# mcu_brd3.net
KiCad netlist of a schematic drawn in EAGLE
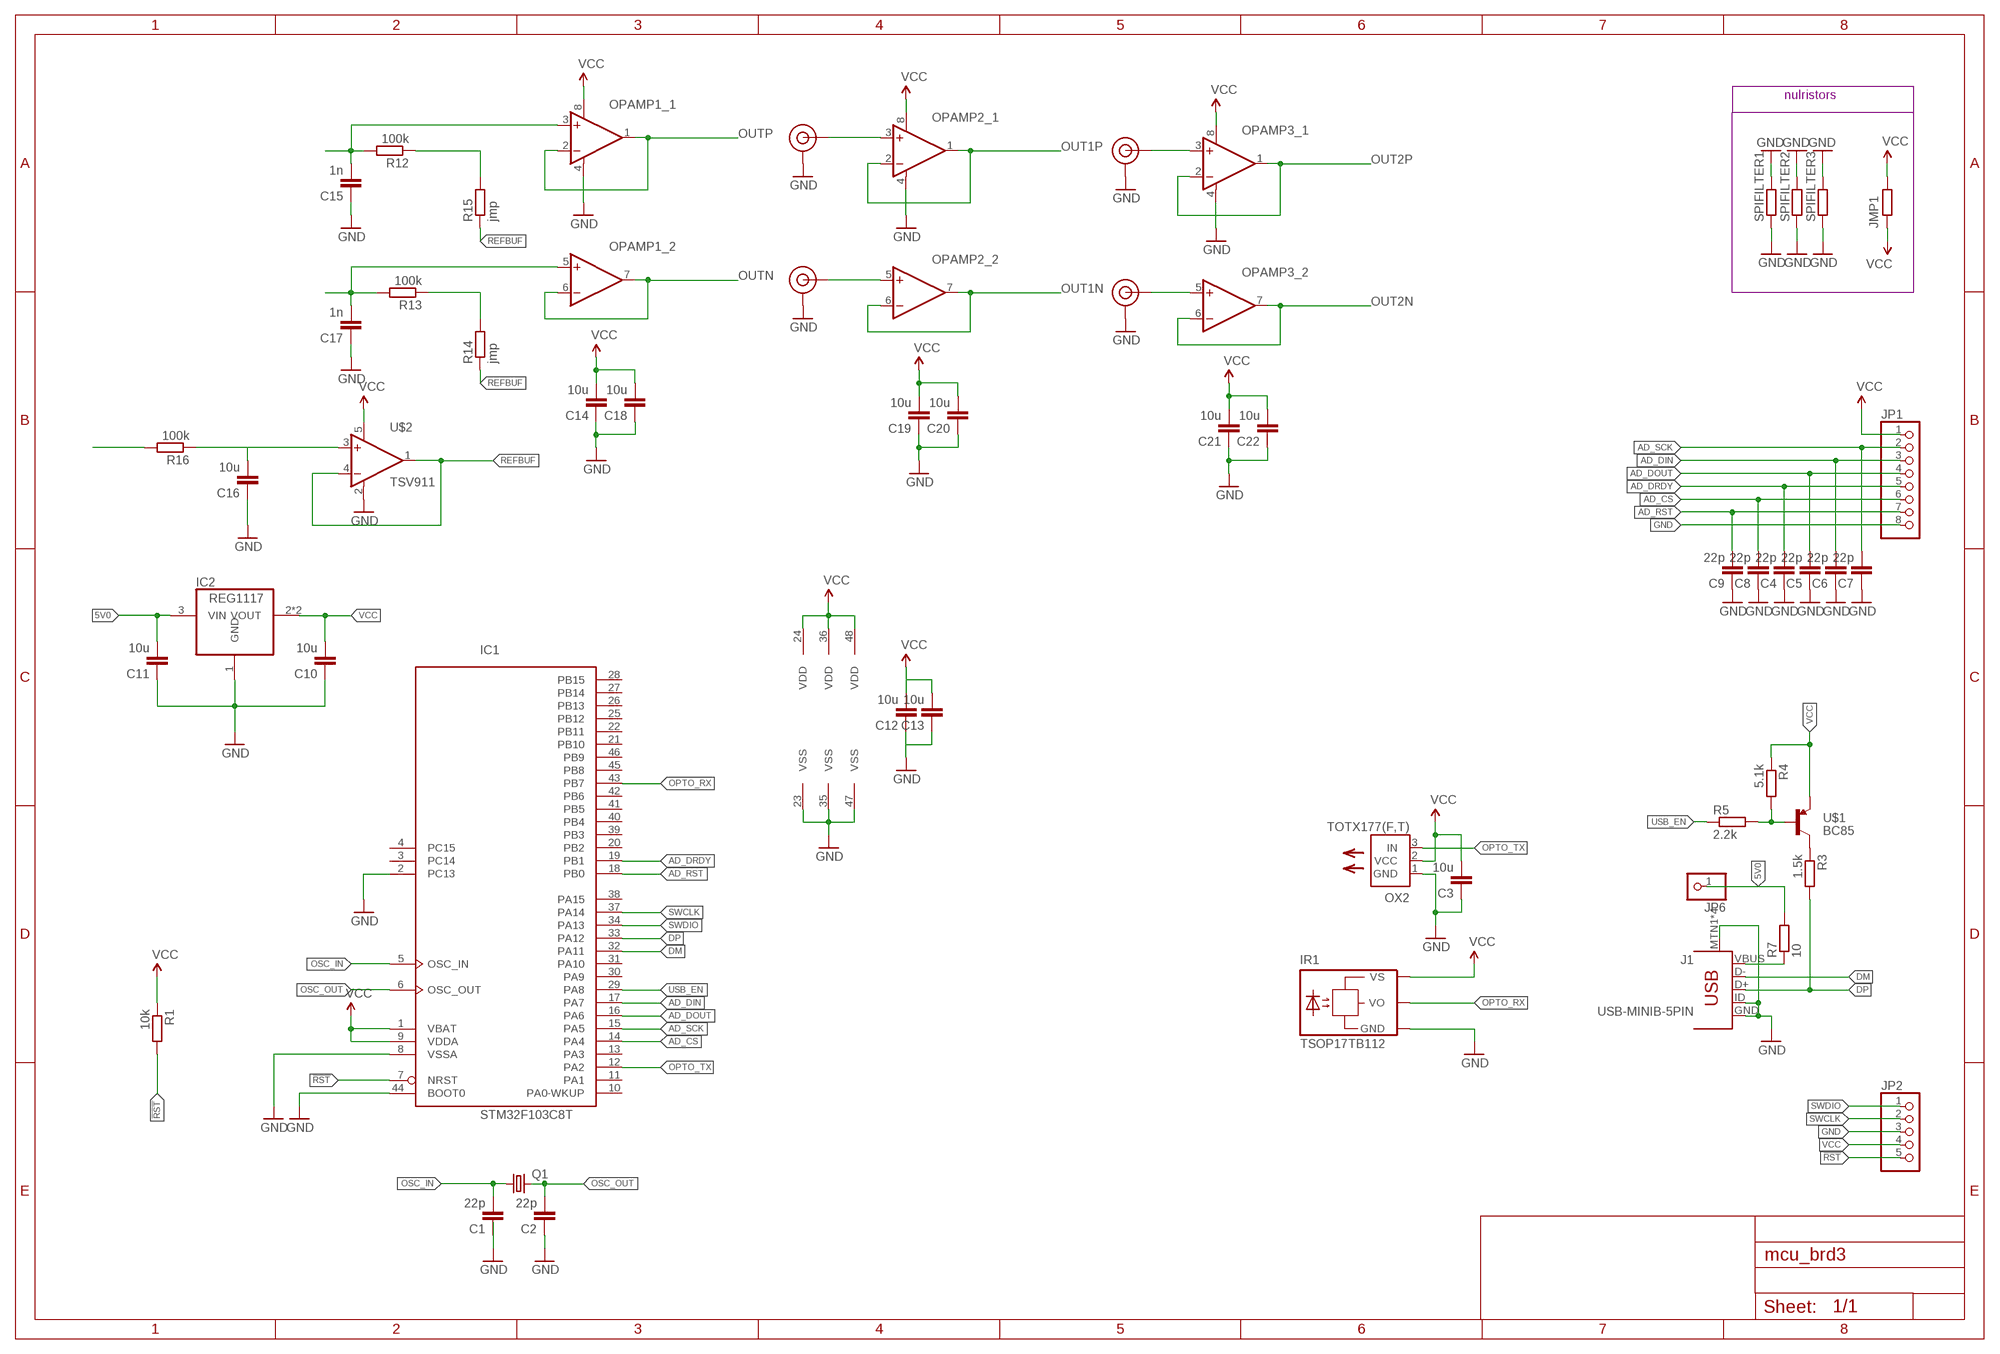
[diagram p0: schematic, sheet 1]

(export (version "E")
  (design (tool "Eeschema 10.0.6"))
  (components
    (comp (ref "C1")
      (value "22p")
      (footprint "eagle-import:C0603")
      (libsource (lib "eagle-import") (part "CC0603"))
    )
    (comp (ref "C2")
      (value "22p")
      (footprint "eagle-import:C0603")
      (libsource (lib "eagle-import") (part "CC0603"))
    )
    (comp (ref "C3")
      (value "10u")
      (footprint "eagle-import:C0603")
      (libsource (lib "eagle-import") (part "CC0603"))
    )
    (comp (ref "C4")
      (value "22p")
      (footprint "eagle-import:C0603")
      (libsource (lib "eagle-import") (part "CC0603"))
    )
    (comp (ref "C5")
      (value "22p")
      (footprint "eagle-import:C0603")
      (libsource (lib "eagle-import") (part "CC0603"))
    )
    (comp (ref "C6")
      (value "22p")
      (footprint "eagle-import:C0603")
      (libsource (lib "eagle-import") (part "CC0603"))
    )
    (comp (ref "C7")
      (value "22p")
      (footprint "eagle-import:C0603")
      (libsource (lib "eagle-import") (part "CC0603"))
    )
    (comp (ref "C8")
      (value "22p")
      (footprint "eagle-import:C0603")
      (libsource (lib "eagle-import") (part "CC0603"))
    )
    (comp (ref "C9")
      (value "22p")
      (footprint "eagle-import:C0603")
      (libsource (lib "eagle-import") (part "CC0603"))
    )
    (comp (ref "C10")
      (value "10u")
      (footprint "eagle-import:C0805")
      (libsource (lib "eagle-import") (part "CC0805"))
    )
    (comp (ref "C11")
      (value "10u")
      (footprint "eagle-import:C0805")
      (libsource (lib "eagle-import") (part "CC0805"))
    )
    (comp (ref "C12")
      (value "10u")
      (footprint "eagle-import:C0805")
      (libsource (lib "eagle-import") (part "CC0805"))
    )
    (comp (ref "C13")
      (value "10u")
      (footprint "eagle-import:C0805")
      (libsource (lib "eagle-import") (part "CC0805"))
    )
    (comp (ref "C14")
      (value "10u")
      (footprint "eagle-import:C0805")
      (libsource (lib "eagle-import") (part "CC0805"))
    )
    (comp (ref "C15")
      (value "1n")
      (footprint "eagle-import:C0603")
      (libsource (lib "eagle-import") (part "CC0603"))
    )
    (comp (ref "C16")
      (value "10u")
      (footprint "eagle-import:C0805")
      (libsource (lib "eagle-import") (part "CC0805"))
    )
    (comp (ref "C17")
      (value "1n")
      (footprint "eagle-import:C0603")
      (libsource (lib "eagle-import") (part "CC0603"))
    )
    (comp (ref "C18")
      (value "10u")
      (footprint "eagle-import:C0805")
      (libsource (lib "eagle-import") (part "CC0805"))
    )
    (comp (ref "C19")
      (value "10u")
      (footprint "eagle-import:C0805")
      (libsource (lib "eagle-import") (part "CC0805"))
    )
    (comp (ref "C20")
      (value "10u")
      (footprint "eagle-import:C0805")
      (libsource (lib "eagle-import") (part "CC0805"))
    )
    (comp (ref "C21")
      (value "10u")
      (footprint "eagle-import:C0805")
      (libsource (lib "eagle-import") (part "CC0805"))
    )
    (comp (ref "C22")
      (value "10u")
      (footprint "eagle-import:C0805")
      (libsource (lib "eagle-import") (part "CC0805"))
    )
    (comp (ref "IC1")
      (value "STM32F103C8T")
      (footprint "eagle-import:LQFP48")
      (libsource (lib "eagle-import") (part "STM32F103CT8"))
    )
    (comp (ref "IC2")
      (value "REG1117")
      (footprint "eagle-import:SOT223")
      (libsource (lib "eagle-import") (part "REG1117"))
    )
    (comp (ref "IR1")
      (value "TSOP17TB112")
      (footprint "eagle-import:1X03")
      (libsource (lib "eagle-import") (part "TSOP17TB112"))
    )
    (comp (ref "J$1")
      (value "SMA_EDGE")
      (footprint "eagle-import:SMA-EDGE")
      (libsource (lib "eagle-import") (part "SMA_EDGE"))
    )
    (comp (ref "J$2")
      (value "SMA_EDGE")
      (footprint "eagle-import:SMA-EDGE")
      (libsource (lib "eagle-import") (part "SMA_EDGE"))
    )
    (comp (ref "J$3")
      (value "SMA_EDGE")
      (footprint "eagle-import:SMA-EDGE")
      (libsource (lib "eagle-import") (part "SMA_EDGE"))
    )
    (comp (ref "J$4")
      (value "SMA_EDGE")
      (footprint "eagle-import:SMA-EDGE")
      (libsource (lib "eagle-import") (part "SMA_EDGE"))
    )
    (comp (ref "J1")
      (value "USB-MINIB-5PIN")
      (footprint "eagle-import:USB-MINIB")
      (libsource (lib "eagle-import") (part "USB-MINIB-5PIN"))
    )
    (comp (ref "JMP1")
      (value "R0603")
      (footprint "eagle-import:0603")
      (libsource (lib "eagle-import") (part "R0603"))
    )
    (comp (ref "JP1")
      (value "PINHD-1X8")
      (footprint "eagle-import:1X08")
      (libsource (lib "eagle-import") (part "PINHD-1X8"))
    )
    (comp (ref "JP2")
      (value "PINHD-1X5")
      (footprint "eagle-import:1X05")
      (libsource (lib "eagle-import") (part "PINHD-1X5"))
    )
    (comp (ref "JP6")
      (value "PINHD-1X1")
      (footprint "eagle-import:1X01")
      (libsource (lib "eagle-import") (part "PINHD-1X1"))
    )
    (comp (ref "OPAMP1")
      (value "LMC662")
      (footprint "eagle-import:SO08")
      (libsource (lib "eagle-import") (part "LMC662"))
    )
    (comp (ref "OPAMP2")
      (value "LMC662")
      (footprint "eagle-import:SO08")
      (libsource (lib "eagle-import") (part "LMC662"))
    )
    (comp (ref "OPAMP3")
      (value "LMC662")
      (footprint "eagle-import:SO08")
      (libsource (lib "eagle-import") (part "LMC662"))
    )
    (comp (ref "OX2")
      (value "TOTX177(F,T)")
      (footprint "eagle-import:TOTX")
      (libsource (lib "eagle-import") (part "TOTX177(F,T)"))
    )
    (comp (ref "Q1")
      (value "CRYSTALHC49UP")
      (footprint "eagle-import:HC49UP")
      (libsource (lib "eagle-import") (part "CRYSTALHC49UP"))
    )
    (comp (ref "R1")
      (value "10k")
      (footprint "eagle-import:0603")
      (libsource (lib "eagle-import") (part "R0603"))
    )
    (comp (ref "R3")
      (value "1.5k")
      (footprint "eagle-import:0603")
      (libsource (lib "eagle-import") (part "R0603"))
    )
    (comp (ref "R4")
      (value "5.1k")
      (footprint "eagle-import:0603")
      (libsource (lib "eagle-import") (part "R0603"))
    )
    (comp (ref "R5")
      (value "2.2k")
      (footprint "eagle-import:0603")
      (libsource (lib "eagle-import") (part "R0603"))
    )
    (comp (ref "R7")
      (value "10")
      (footprint "eagle-import:R0805")
      (libsource (lib "eagle-import") (part "R0805"))
    )
    (comp (ref "R12")
      (value "100k")
      (footprint "eagle-import:0603")
      (libsource (lib "eagle-import") (part "R0603"))
    )
    (comp (ref "R13")
      (value "100k")
      (footprint "eagle-import:0603")
      (libsource (lib "eagle-import") (part "R0603"))
    )
    (comp (ref "R14")
      (value "jmp")
      (footprint "eagle-import:0603")
      (libsource (lib "eagle-import") (part "R0603"))
    )
    (comp (ref "R15")
      (value "jmp")
      (footprint "eagle-import:0603")
      (libsource (lib "eagle-import") (part "R0603"))
    )
    (comp (ref "R16")
      (value "100k")
      (footprint "eagle-import:0603")
      (libsource (lib "eagle-import") (part "R0603"))
    )
    (comp (ref "SPIFILTER1")
      (value "R0603")
      (footprint "eagle-import:0603")
      (libsource (lib "eagle-import") (part "R0603"))
    )
    (comp (ref "SPIFILTER2")
      (value "R0603")
      (footprint "eagle-import:0603")
      (libsource (lib "eagle-import") (part "R0603"))
    )
    (comp (ref "SPIFILTER3")
      (value "R0603")
      (footprint "eagle-import:0603")
      (libsource (lib "eagle-import") (part "R0603"))
    )
    (comp (ref "U$1")
      (value "BC85")
      (footprint "eagle-import:SOT23")
      (libsource (lib "eagle-import") (part "BC85"))
    )
    (comp (ref "U$2")
      (value "TSV911")
      (footprint "eagle-import:SOT23-5L")
      (libsource (lib "eagle-import") (part "TSV911"))
    )
  )
  (nets
    (net (code "1") (name "/OUT1N") (class "Default")
      (node (ref "OPAMP2") (pin "6") (pinfunction "-IN_6") (pintype "input"))
      (node (ref "OPAMP2") (pin "7") (pinfunction "OUT_7") (pintype "output"))
    )
    (net (code "2") (name "/OUT1P") (class "Default")
      (node (ref "OPAMP2") (pin "1") (pinfunction "OUT_1") (pintype "output"))
      (node (ref "OPAMP2") (pin "2") (pinfunction "-IN_2") (pintype "input"))
    )
    (net (code "3") (name "/OUT2N") (class "Default")
      (node (ref "OPAMP3") (pin "6") (pinfunction "-IN_6") (pintype "input"))
      (node (ref "OPAMP3") (pin "7") (pinfunction "OUT_7") (pintype "output"))
    )
    (net (code "4") (name "/OUT2P") (class "Default")
      (node (ref "OPAMP3") (pin "1") (pinfunction "OUT_1") (pintype "output"))
      (node (ref "OPAMP3") (pin "2") (pinfunction "-IN_2") (pintype "input"))
    )
    (net (code "5") (name "/OUTN") (class "Default")
      (node (ref "OPAMP1") (pin "6") (pinfunction "-IN_6") (pintype "input"))
      (node (ref "OPAMP1") (pin "7") (pinfunction "OUT_7") (pintype "output"))
    )
    (net (code "6") (name "/OUTP") (class "Default")
      (node (ref "OPAMP1") (pin "1") (pinfunction "OUT_1") (pintype "output"))
      (node (ref "OPAMP1") (pin "2") (pinfunction "-IN_2") (pintype "input"))
    )
    (net (code "7") (name "/~{RST}") (class "Default")
      (node (ref "IC1") (pin "7") (pinfunction "NRST_7") (pintype "bidirectional"))
      (node (ref "JP2") (pin "5") (pinfunction "5_5") (pintype "passive"))
      (node (ref "R1") (pin "2") (pinfunction "2_2") (pintype "passive"))
    )
    (net (code "8") (name "5V0") (class "Default")
      (node (ref "C11") (pin "2") (pinfunction "2_2") (pintype "passive"))
      (node (ref "IC2") (pin "3") (pinfunction "VIN_3") (pintype "input"))
      (node (ref "JP6") (pin "1") (pinfunction "1_1") (pintype "passive"))
      (node (ref "R7") (pin "2") (pinfunction "2_2") (pintype "passive"))
    )
    (net (code "9") (name "AD_CS") (class "Default")
      (node (ref "C8") (pin "2") (pinfunction "2_2") (pintype "passive"))
      (node (ref "IC1") (pin "14") (pinfunction "PA4_14") (pintype "bidirectional"))
      (node (ref "JP1") (pin "6") (pinfunction "6_6") (pintype "passive"))
    )
    (net (code "10") (name "AD_DIN") (class "Default")
      (node (ref "C6") (pin "2") (pinfunction "2_2") (pintype "passive"))
      (node (ref "IC1") (pin "17") (pinfunction "PA7_17") (pintype "bidirectional"))
      (node (ref "JP1") (pin "3") (pinfunction "3_3") (pintype "passive"))
    )
    (net (code "11") (name "AD_DOUT") (class "Default")
      (node (ref "C5") (pin "2") (pinfunction "2_2") (pintype "passive"))
      (node (ref "IC1") (pin "16") (pinfunction "PA6_16") (pintype "bidirectional"))
      (node (ref "JP1") (pin "4") (pinfunction "4_4") (pintype "passive"))
    )
    (net (code "12") (name "AD_DRDY") (class "Default")
      (node (ref "C4") (pin "2") (pinfunction "2_2") (pintype "passive"))
      (node (ref "IC1") (pin "19") (pinfunction "PB1_19") (pintype "bidirectional"))
      (node (ref "JP1") (pin "5") (pinfunction "5_5") (pintype "passive"))
    )
    (net (code "13") (name "AD_RST") (class "Default")
      (node (ref "C9") (pin "2") (pinfunction "2_2") (pintype "passive"))
      (node (ref "IC1") (pin "18") (pinfunction "PB0_18") (pintype "bidirectional"))
      (node (ref "JP1") (pin "7") (pinfunction "7_7") (pintype "passive"))
    )
    (net (code "14") (name "AD_SCK") (class "Default")
      (node (ref "C7") (pin "2") (pinfunction "2_2") (pintype "passive"))
      (node (ref "IC1") (pin "15") (pinfunction "PA5_15") (pintype "bidirectional"))
      (node (ref "JP1") (pin "2") (pinfunction "2_2") (pintype "passive"))
    )
    (net (code "15") (name "DM") (class "Default")
      (node (ref "IC1") (pin "32") (pinfunction "PA11_32") (pintype "bidirectional"))
      (node (ref "J1") (pin "D-") (pinfunction "D-_D-") (pintype "bidirectional"))
    )
    (net (code "16") (name "DP") (class "Default")
      (node (ref "IC1") (pin "33") (pinfunction "PA12_33") (pintype "bidirectional"))
      (node (ref "J1") (pin "D+") (pinfunction "D+_D+") (pintype "bidirectional"))
      (node (ref "R3") (pin "2") (pinfunction "2_2") (pintype "passive"))
    )
    (net (code "17") (name "GND") (class "Default")
      (node (ref "C1") (pin "1") (pinfunction "1_1") (pintype "passive"))
      (node (ref "C10") (pin "1") (pinfunction "1_1") (pintype "passive"))
      (node (ref "C11") (pin "1") (pinfunction "1_1") (pintype "passive"))
      (node (ref "C12") (pin "1") (pinfunction "1_1") (pintype "passive"))
      (node (ref "C13") (pin "1") (pinfunction "1_1") (pintype "passive"))
      (node (ref "C14") (pin "1") (pinfunction "1_1") (pintype "passive"))
      (node (ref "C15") (pin "1") (pinfunction "1_1") (pintype "passive"))
      (node (ref "C16") (pin "1") (pinfunction "1_1") (pintype "passive"))
      (node (ref "C17") (pin "1") (pinfunction "1_1") (pintype "passive"))
      (node (ref "C18") (pin "1") (pinfunction "1_1") (pintype "passive"))
      (node (ref "C19") (pin "1") (pinfunction "1_1") (pintype "passive"))
      (node (ref "C2") (pin "1") (pinfunction "1_1") (pintype "passive"))
      (node (ref "C20") (pin "1") (pinfunction "1_1") (pintype "passive"))
      (node (ref "C21") (pin "1") (pinfunction "1_1") (pintype "passive"))
      (node (ref "C22") (pin "1") (pinfunction "1_1") (pintype "passive"))
      (node (ref "C3") (pin "1") (pinfunction "1_1") (pintype "passive"))
      (node (ref "C4") (pin "1") (pinfunction "1_1") (pintype "passive"))
      (node (ref "C5") (pin "1") (pinfunction "1_1") (pintype "passive"))
      (node (ref "C6") (pin "1") (pinfunction "1_1") (pintype "passive"))
      (node (ref "C7") (pin "1") (pinfunction "1_1") (pintype "passive"))
      (node (ref "C8") (pin "1") (pinfunction "1_1") (pintype "passive"))
      (node (ref "C9") (pin "1") (pinfunction "1_1") (pintype "passive"))
      (node (ref "IC1") (pin "2") (pinfunction "PC13_2") (pintype "bidirectional"))
      (node (ref "IC1") (pin "23") (pinfunction "VSS_23") (pintype "power_in"))
      (node (ref "IC1") (pin "35") (pinfunction "VSS_35") (pintype "power_in"))
      (node (ref "IC1") (pin "44") (pinfunction "BOOT0_44") (pintype "input"))
      (node (ref "IC1") (pin "47") (pinfunction "VSS_47") (pintype "power_in"))
      (node (ref "IC1") (pin "8") (pinfunction "VSSA_8") (pintype "power_in"))
      (node (ref "IC2") (pin "1") (pinfunction "GND_1") (pintype "power_in"))
      (node (ref "IR1") (pin "3") (pinfunction "GND_3") (pintype "power_in"))
      (node (ref "J$1") (pin "GND@0") (pinfunction "GND_GND@0") (pintype "bidirectional"))
      (node (ref "J$1") (pin "GND@1") (pinfunction "GND_GND@1") (pintype "bidirectional"))
      (node (ref "J$1") (pin "GND@2") (pinfunction "GND_GND@2") (pintype "bidirectional"))
      (node (ref "J$1") (pin "GND@3") (pinfunction "GND_GND@3") (pintype "bidirectional"))
      (node (ref "J$2") (pin "GND@0") (pinfunction "GND_GND@0") (pintype "bidirectional"))
      (node (ref "J$2") (pin "GND@1") (pinfunction "GND_GND@1") (pintype "bidirectional"))
      (node (ref "J$2") (pin "GND@2") (pinfunction "GND_GND@2") (pintype "bidirectional"))
      (node (ref "J$2") (pin "GND@3") (pinfunction "GND_GND@3") (pintype "bidirectional"))
      (node (ref "J$3") (pin "GND@0") (pinfunction "GND_GND@0") (pintype "bidirectional"))
      (node (ref "J$3") (pin "GND@1") (pinfunction "GND_GND@1") (pintype "bidirectional"))
      (node (ref "J$3") (pin "GND@2") (pinfunction "GND_GND@2") (pintype "bidirectional"))
      (node (ref "J$3") (pin "GND@3") (pinfunction "GND_GND@3") (pintype "bidirectional"))
      (node (ref "J$4") (pin "GND@0") (pinfunction "GND_GND@0") (pintype "bidirectional"))
      (node (ref "J$4") (pin "GND@1") (pinfunction "GND_GND@1") (pintype "bidirectional"))
      (node (ref "J$4") (pin "GND@2") (pinfunction "GND_GND@2") (pintype "bidirectional"))
      (node (ref "J$4") (pin "GND@3") (pinfunction "GND_GND@3") (pintype "bidirectional"))
      (node (ref "J1") (pin "GND") (pinfunction "GND_GND") (pintype "bidirectional"))
      (node (ref "J1") (pin "ID") (pinfunction "ID_ID") (pintype "bidirectional"))
      (node (ref "J1") (pin "MTN1") (pinfunction "MTN1_MTN1") (pintype "bidirectional"))
      (node (ref "J1") (pin "MTN2") (pinfunction "MTN1_MTN2") (pintype "bidirectional"))
      (node (ref "J1") (pin "MTN3") (pinfunction "MTN1_MTN3") (pintype "bidirectional"))
      (node (ref "J1") (pin "MTN4") (pinfunction "MTN1_MTN4") (pintype "bidirectional"))
      (node (ref "JP1") (pin "8") (pinfunction "8_8") (pintype "passive"))
      (node (ref "JP2") (pin "3") (pinfunction "3_3") (pintype "passive"))
      (node (ref "OPAMP1") (pin "4") (pinfunction "V-_4") (pintype "power_in"))
      (node (ref "OPAMP2") (pin "4") (pinfunction "V-_4") (pintype "power_in"))
      (node (ref "OPAMP3") (pin "4") (pinfunction "V-_4") (pintype "power_in"))
      (node (ref "OX2") (pin "1") (pinfunction "GND_1") (pintype "power_in"))
      (node (ref "SPIFILTER1") (pin "1") (pinfunction "1_1") (pintype "passive"))
      (node (ref "SPIFILTER1") (pin "2") (pinfunction "2_2") (pintype "passive"))
      (node (ref "SPIFILTER2") (pin "1") (pinfunction "1_1") (pintype "passive"))
      (node (ref "SPIFILTER2") (pin "2") (pinfunction "2_2") (pintype "passive"))
      (node (ref "SPIFILTER3") (pin "1") (pinfunction "1_1") (pintype "passive"))
      (node (ref "SPIFILTER3") (pin "2") (pinfunction "2_2") (pintype "passive"))
      (node (ref "U$2") (pin "2") (pinfunction "V-_2") (pintype "power_in"))
    )
    (net (code "18") (name "Net-(J$1-SIGNAL)") (class "Default")
      (node (ref "J$1") (pin "SIG") (pinfunction "SIGNAL_SIG") (pintype "bidirectional"))
      (node (ref "OPAMP2") (pin "3") (pinfunction "+IN_3") (pintype "input"))
    )
    (net (code "19") (name "Net-(J$2-SIGNAL)") (class "Default")
      (node (ref "J$2") (pin "SIG") (pinfunction "SIGNAL_SIG") (pintype "bidirectional"))
      (node (ref "OPAMP2") (pin "5") (pinfunction "+IN_5") (pintype "input"))
    )
    (net (code "20") (name "Net-(J$3-SIGNAL)") (class "Default")
      (node (ref "J$3") (pin "SIG") (pinfunction "SIGNAL_SIG") (pintype "bidirectional"))
      (node (ref "OPAMP3") (pin "3") (pinfunction "+IN_3") (pintype "input"))
    )
    (net (code "21") (name "Net-(J$4-SIGNAL)") (class "Default")
      (node (ref "J$4") (pin "SIG") (pinfunction "SIGNAL_SIG") (pintype "bidirectional"))
      (node (ref "OPAMP3") (pin "5") (pinfunction "+IN_5") (pintype "input"))
    )
    (net (code "22") (name "Net-(J1-PadVBUS)") (class "Default")
      (node (ref "J1") (pin "VBUS") (pinfunction "VBUS_VBUS") (pintype "bidirectional"))
      (node (ref "R7") (pin "1") (pinfunction "1_1") (pintype "passive"))
    )
    (net (code "23") (name "Net-(OPAMP1A-+IN)") (class "Default")
      (node (ref "C15") (pin "2") (pinfunction "2_2") (pintype "passive"))
      (node (ref "OPAMP1") (pin "3") (pinfunction "+IN_3") (pintype "input"))
      (node (ref "R12") (pin "2") (pinfunction "2_2") (pintype "passive"))
    )
    (net (code "24") (name "Net-(OPAMP1B-+IN)") (class "Default")
      (node (ref "C17") (pin "2") (pinfunction "2_2") (pintype "passive"))
      (node (ref "OPAMP1") (pin "5") (pinfunction "+IN_5") (pintype "input"))
      (node (ref "R13") (pin "2") (pinfunction "2_2") (pintype "passive"))
    )
    (net (code "25") (name "Net-(R12-Pad1)") (class "Default")
      (node (ref "R12") (pin "1") (pinfunction "1_1") (pintype "passive"))
      (node (ref "R15") (pin "2") (pinfunction "2_2") (pintype "passive"))
    )
    (net (code "26") (name "Net-(R13-Pad1)") (class "Default")
      (node (ref "R13") (pin "1") (pinfunction "1_1") (pintype "passive"))
      (node (ref "R14") (pin "2") (pinfunction "2_2") (pintype "passive"))
    )
    (net (code "27") (name "Net-(U$1-B)") (class "Default")
      (node (ref "R4") (pin "2") (pinfunction "2_2") (pintype "passive"))
      (node (ref "R5") (pin "2") (pinfunction "2_2") (pintype "passive"))
      (node (ref "U$1") (pin "1") (pinfunction "B_1") (pintype "passive"))
    )
    (net (code "28") (name "Net-(U$1-C)") (class "Default")
      (node (ref "R3") (pin "1") (pinfunction "1_1") (pintype "passive"))
      (node (ref "U$1") (pin "3") (pinfunction "C_3") (pintype "passive"))
    )
    (net (code "29") (name "Net-(U$2-+IN)") (class "Default")
      (node (ref "C16") (pin "2") (pinfunction "2_2") (pintype "passive"))
      (node (ref "R16") (pin "1") (pinfunction "1_1") (pintype "passive"))
      (node (ref "U$2") (pin "3") (pinfunction "+IN_3") (pintype "input"))
    )
    (net (code "30") (name "OPTO_RX") (class "Default")
      (node (ref "IC1") (pin "43") (pinfunction "PB7_43") (pintype "bidirectional"))
      (node (ref "IR1") (pin "1") (pinfunction "VO_1") (pintype "open_collector"))
    )
    (net (code "31") (name "OPTO_TX") (class "Default")
      (node (ref "IC1") (pin "12") (pinfunction "PA2_12") (pintype "bidirectional"))
      (node (ref "OX2") (pin "3") (pinfunction "IN_3") (pintype "input"))
    )
    (net (code "32") (name "OSC_IN") (class "Default")
      (node (ref "C1") (pin "2") (pinfunction "2_2") (pintype "passive"))
      (node (ref "IC1") (pin "5") (pinfunction "OSC_IN_5") (pintype "bidirectional"))
      (node (ref "Q1") (pin "1") (pinfunction "1_1") (pintype "passive"))
    )
    (net (code "33") (name "OSC_OUT") (class "Default")
      (node (ref "C2") (pin "2") (pinfunction "2_2") (pintype "passive"))
      (node (ref "IC1") (pin "6") (pinfunction "OSC_OUT_6") (pintype "bidirectional"))
      (node (ref "Q1") (pin "2") (pinfunction "2_2") (pintype "passive"))
    )
    (net (code "34") (name "REFBUF") (class "Default")
      (node (ref "R14") (pin "1") (pinfunction "1_1") (pintype "passive"))
      (node (ref "R15") (pin "1") (pinfunction "1_1") (pintype "passive"))
      (node (ref "U$2") (pin "1") (pinfunction "OUT_1") (pintype "output"))
      (node (ref "U$2") (pin "4") (pinfunction "-IN_4") (pintype "input"))
    )
    (net (code "35") (name "SWCLK") (class "Default")
      (node (ref "IC1") (pin "37") (pinfunction "PA14_37") (pintype "bidirectional"))
      (node (ref "JP2") (pin "2") (pinfunction "2_2") (pintype "passive"))
    )
    (net (code "36") (name "SWDIO") (class "Default")
      (node (ref "IC1") (pin "34") (pinfunction "PA13_34") (pintype "bidirectional"))
      (node (ref "JP2") (pin "1") (pinfunction "1_1") (pintype "passive"))
    )
    (net (code "37") (name "USB_EN") (class "Default")
      (node (ref "IC1") (pin "29") (pinfunction "PA8_29") (pintype "bidirectional"))
      (node (ref "R5") (pin "1") (pinfunction "1_1") (pintype "passive"))
    )
    (net (code "38") (name "VCC") (class "Default")
      (node (ref "C10") (pin "2") (pinfunction "2_2") (pintype "passive"))
      (node (ref "C12") (pin "2") (pinfunction "2_2") (pintype "passive"))
      (node (ref "C13") (pin "2") (pinfunction "2_2") (pintype "passive"))
      (node (ref "C14") (pin "2") (pinfunction "2_2") (pintype "passive"))
      (node (ref "C18") (pin "2") (pinfunction "2_2") (pintype "passive"))
      (node (ref "C19") (pin "2") (pinfunction "2_2") (pintype "passive"))
      (node (ref "C20") (pin "2") (pinfunction "2_2") (pintype "passive"))
      (node (ref "C21") (pin "2") (pinfunction "2_2") (pintype "passive"))
      (node (ref "C22") (pin "2") (pinfunction "2_2") (pintype "passive"))
      (node (ref "C3") (pin "2") (pinfunction "2_2") (pintype "passive"))
      (node (ref "IC1") (pin "1") (pinfunction "VBAT_1") (pintype "power_in"))
      (node (ref "IC1") (pin "24") (pinfunction "VDD_24") (pintype "power_in"))
      (node (ref "IC1") (pin "36") (pinfunction "VDD_36") (pintype "power_in"))
      (node (ref "IC1") (pin "48") (pinfunction "VDD_48") (pintype "power_in"))
      (node (ref "IC1") (pin "9") (pinfunction "VDDA_9") (pintype "power_in"))
      (node (ref "IC2") (pin "2") (pinfunction "VOUT_2") (pintype "output"))
      (node (ref "IC2") (pin "4") (pinfunction "VOUT_4") (pintype "output"))
      (node (ref "IR1") (pin "2") (pinfunction "VS_2") (pintype "power_in"))
      (node (ref "JMP1") (pin "1") (pinfunction "1_1") (pintype "passive"))
      (node (ref "JMP1") (pin "2") (pinfunction "2_2") (pintype "passive"))
      (node (ref "JP1") (pin "1") (pinfunction "1_1") (pintype "passive"))
      (node (ref "JP2") (pin "4") (pinfunction "4_4") (pintype "passive"))
      (node (ref "OPAMP1") (pin "8") (pinfunction "V+_8") (pintype "power_in"))
      (node (ref "OPAMP2") (pin "8") (pinfunction "V+_8") (pintype "power_in"))
      (node (ref "OPAMP3") (pin "8") (pinfunction "V+_8") (pintype "power_in"))
      (node (ref "OX2") (pin "2") (pinfunction "VCC_2") (pintype "power_in"))
      (node (ref "R1") (pin "1") (pinfunction "1_1") (pintype "passive"))
      (node (ref "R4") (pin "1") (pinfunction "1_1") (pintype "passive"))
      (node (ref "U$1") (pin "2") (pinfunction "E_2") (pintype "passive"))
      (node (ref "U$2") (pin "5") (pinfunction "V+_5") (pintype "power_in"))
    )
    (net (code "39") (name "unconnected-(IC1A-PA0-WKUP-Pad10)") (class "Default")
      (node (ref "IC1") (pin "10") (pinfunction "PA0-WKUP_10") (pintype "bidirectional"))
    )
    (net (code "40") (name "unconnected-(IC1A-PA1-Pad11)") (class "Default")
      (node (ref "IC1") (pin "11") (pinfunction "PA1_11") (pintype "bidirectional"))
    )
    (net (code "41") (name "unconnected-(IC1A-PA3-Pad13)") (class "Default")
      (node (ref "IC1") (pin "13") (pinfunction "PA3_13") (pintype "bidirectional"))
    )
    (net (code "42") (name "unconnected-(IC1A-PA9-Pad30)") (class "Default")
      (node (ref "IC1") (pin "30") (pinfunction "PA9_30") (pintype "bidirectional"))
    )
    (net (code "43") (name "unconnected-(IC1A-PA10-Pad31)") (class "Default")
      (node (ref "IC1") (pin "31") (pinfunction "PA10_31") (pintype "bidirectional"))
    )
    (net (code "44") (name "unconnected-(IC1A-PA15-Pad38)") (class "Default")
      (node (ref "IC1") (pin "38") (pinfunction "PA15_38") (pintype "bidirectional"))
    )
    (net (code "45") (name "unconnected-(IC1A-PB2-Pad20)") (class "Default")
      (node (ref "IC1") (pin "20") (pinfunction "PB2_20") (pintype "bidirectional"))
    )
    (net (code "46") (name "unconnected-(IC1A-PB3-Pad39)") (class "Default")
      (node (ref "IC1") (pin "39") (pinfunction "PB3_39") (pintype "bidirectional"))
    )
    (net (code "47") (name "unconnected-(IC1A-PB4-Pad40)") (class "Default")
      (node (ref "IC1") (pin "40") (pinfunction "PB4_40") (pintype "bidirectional"))
    )
    (net (code "48") (name "unconnected-(IC1A-PB5-Pad41)") (class "Default")
      (node (ref "IC1") (pin "41") (pinfunction "PB5_41") (pintype "bidirectional"))
    )
    (net (code "49") (name "unconnected-(IC1A-PB6-Pad42)") (class "Default")
      (node (ref "IC1") (pin "42") (pinfunction "PB6_42") (pintype "bidirectional"))
    )
    (net (code "50") (name "unconnected-(IC1A-PB8-Pad45)") (class "Default")
      (node (ref "IC1") (pin "45") (pinfunction "PB8_45") (pintype "bidirectional"))
    )
    (net (code "51") (name "unconnected-(IC1A-PB9-Pad46)") (class "Default")
      (node (ref "IC1") (pin "46") (pinfunction "PB9_46") (pintype "bidirectional"))
    )
    (net (code "52") (name "unconnected-(IC1A-PB10-Pad21)") (class "Default")
      (node (ref "IC1") (pin "21") (pinfunction "PB10_21") (pintype "bidirectional"))
    )
    (net (code "53") (name "unconnected-(IC1A-PB11-Pad22)") (class "Default")
      (node (ref "IC1") (pin "22") (pinfunction "PB11_22") (pintype "bidirectional"))
    )
    (net (code "54") (name "unconnected-(IC1A-PB12-Pad25)") (class "Default")
      (node (ref "IC1") (pin "25") (pinfunction "PB12_25") (pintype "bidirectional"))
    )
    (net (code "55") (name "unconnected-(IC1A-PB13-Pad26)") (class "Default")
      (node (ref "IC1") (pin "26") (pinfunction "PB13_26") (pintype "bidirectional"))
    )
    (net (code "56") (name "unconnected-(IC1A-PB14-Pad27)") (class "Default")
      (node (ref "IC1") (pin "27") (pinfunction "PB14_27") (pintype "bidirectional"))
    )
    (net (code "57") (name "unconnected-(IC1A-PB15-Pad28)") (class "Default")
      (node (ref "IC1") (pin "28") (pinfunction "PB15_28") (pintype "bidirectional"))
    )
    (net (code "58") (name "unconnected-(IC1A-PC14-Pad3)") (class "Default")
      (node (ref "IC1") (pin "3") (pinfunction "PC14_3") (pintype "bidirectional"))
    )
    (net (code "59") (name "unconnected-(IC1A-PC15-Pad4)") (class "Default")
      (node (ref "IC1") (pin "4") (pinfunction "PC15_4") (pintype "bidirectional"))
    )
    (net (code "60") (name "unconnected-(R16-Pad2)") (class "Default")
      (node (ref "R16") (pin "2") (pinfunction "2_2") (pintype "passive"))
    )
  )
)
